# npm1300_qeaa_config3.net
KiCad netlist of a schematic drawn in Altium Designer
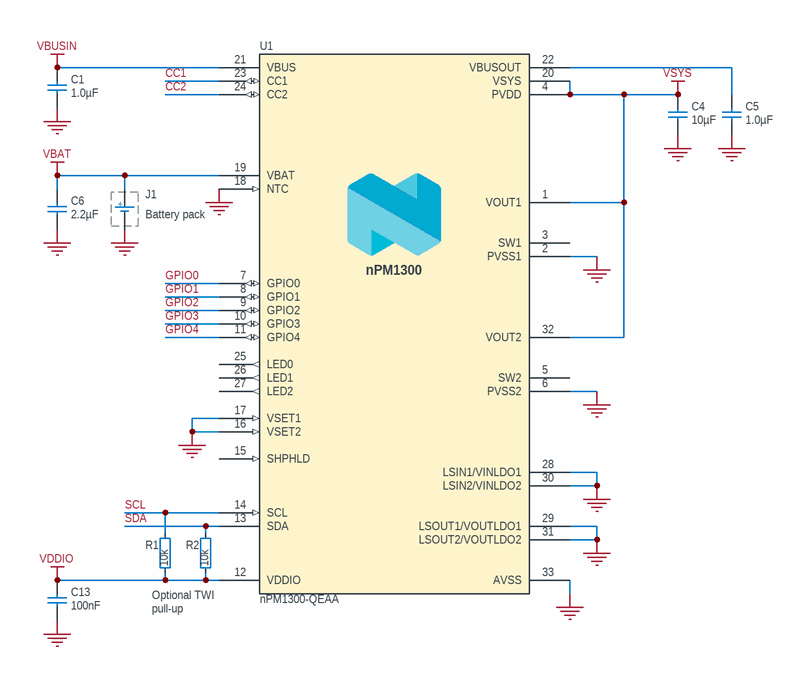
[diagram p0: npm1300_qeaa_config3.SchDoc]

(export (version "E")
  (design (tool "Eeschema 10.0.6"))
  (components
    (comp (ref "C1")
      (value "1.0µF")
      (footprint "CAPC1608X06L")
      (description "Capacitor, Ceramic, 1.0µF 10V X5R 0603,±10%")
      (fields
        (field (name "PART NUMBER") "C0603-1µ0-10V-X5R")
        (field (name "MANUFACTURER") "N.A.")
        (field (name "AUTHOR") "getr")
      )
      (libsource (lib "AltiumLib") (part "CAP"))
    )
    (comp (ref "C4")
      (value "10µF")
      (footprint "CAPC1608X06L")
      (description "Capacitor, X5R, ±20%")
      (fields
        (field (name "PART NUMBER") "C0603-10µ")
        (field (name "MANUFACTURER") "N.A.")
        (field (name "AUTHOR") "rsk")
      )
      (libsource (lib "AltiumLib") (part "CAP"))
    )
    (comp (ref "C5")
      (value "1.0µF")
      (footprint "CAPC1608X06L")
      (description "Capacitor, Ceramic, 1.0µF 10V X5R 0603,±10%")
      (fields
        (field (name "PART NUMBER") "C0603-1µ0-10V-X5R")
        (field (name "MANUFACTURER") "N.A.")
        (field (name "AUTHOR") "getr")
      )
      (libsource (lib "AltiumLib") (part "CAP"))
    )
    (comp (ref "C6")
      (value "2.2µF")
      (footprint "CAPC1608X06L")
      (description "Capacitor, Ceramic, X7R, ±10%, 16V")
      (fields
        (field (name "PART NUMBER") "C0603-2.2µ-16V-X7R")
        (field (name "MANUFACTURER") "Taiyo Yuden")
        (field (name "AUTHOR") "rsk")
      )
      (libsource (lib "AltiumLib") (part "CAP"))
    )
    (comp (ref "C13")
      (value "100nF")
      (footprint "CAPC0603X03L_C")
      (description "Capacitor, X5R, ±10%")
      (fields
        (field (name "PART NUMBER") "C0201-100n")
        (field (name "MANUFACTURER") "N.A.")
        (field (name "AUTHOR") "rsk")
      )
      (libsource (lib "AltiumLib") (part "CAP"))
    )
    (comp (ref "J1")
      (value "Battery pack")
      (footprint "TP_2x1mm_TH")
      (fields
        (field (name "PART NUMBER") "Battery_TP")
        (field (name "MANUFACTURER") "N.A.")
        (field (name "AUTHOR") "rsk")
      )
      (libsource (lib "AltiumLib") (part "Battery_pack"))
    )
    (comp (ref "R1")
      (value "10k")
      (footprint "RESC0603X03L_C")
      (description "Resistor, ±1%, 0.05W")
      (fields
        (field (name "PART NUMBER") "R0201-10k")
        (field (name "MANUFACTURER") "N.A.")
        (field (name "AUTHOR") "rsk")
      )
      (libsource (lib "AltiumLib") (part "RES"))
    )
    (comp (ref "R2")
      (value "10k")
      (footprint "RESC0603X03L_C")
      (description "Resistor, ±1%, 0.05W")
      (fields
        (field (name "PART NUMBER") "R0201-10k")
        (field (name "MANUFACTURER") "N.A.")
        (field (name "AUTHOR") "rsk")
      )
      (libsource (lib "AltiumLib") (part "RES"))
    )
    (comp (ref "U1")
      (value "nPM1300-QEAA")
      (footprint "Nordic_QFN50P500X500X90-33N")
      (fields (field (name "MANUFACTURER") "Nordic Semiconductor") (field (name "AUTHOR") "eisk"))
      (libsource (lib "AltiumLib") (part "nPM1300_QEAA"))
    )
  )
  (nets
    (net (code "1") (name "/CC1") (class "Default")
      (node (ref "U1") (pin "23") (pinfunction "CC1_23") (pintype "bidirectional"))
    )
    (net (code "2") (name "/CC2") (class "Default")
      (node (ref "U1") (pin "24") (pinfunction "CC2_24") (pintype "bidirectional"))
    )
    (net (code "3") (name "/GPIO0") (class "Default")
      (node (ref "U1") (pin "7") (pinfunction "GPIO0_7") (pintype "bidirectional"))
    )
    (net (code "4") (name "/GPIO1") (class "Default")
      (node (ref "U1") (pin "8") (pinfunction "GPIO1_8") (pintype "bidirectional"))
    )
    (net (code "5") (name "/GPIO2") (class "Default")
      (node (ref "U1") (pin "9") (pinfunction "GPIO2_9") (pintype "bidirectional"))
    )
    (net (code "6") (name "/GPIO3") (class "Default")
      (node (ref "U1") (pin "10") (pinfunction "GPIO3_10") (pintype "bidirectional"))
    )
    (net (code "7") (name "/GPIO4") (class "Default")
      (node (ref "U1") (pin "11") (pinfunction "GPIO4_11") (pintype "bidirectional"))
    )
    (net (code "8") (name "/SCL") (class "Default")
      (node (ref "R1") (pin "1") (pinfunction "1_1") (pintype "passive"))
      (node (ref "U1") (pin "14") (pinfunction "SCL_14") (pintype "input"))
    )
    (net (code "9") (name "/SDA") (class "Default")
      (node (ref "R2") (pin "1") (pinfunction "1_1") (pintype "passive"))
      (node (ref "U1") (pin "13") (pinfunction "SDA_13") (pintype "open_collector"))
    )
    (net (code "10") (name "GND") (class "Default")
      (node (ref "C1") (pin "1") (pinfunction "1_1") (pintype "passive"))
      (node (ref "C13") (pin "2") (pinfunction "2_2") (pintype "passive"))
      (node (ref "C4") (pin "1") (pinfunction "1_1") (pintype "passive"))
      (node (ref "C5") (pin "1") (pinfunction "1_1") (pintype "passive"))
      (node (ref "C6") (pin "1") (pinfunction "1_1") (pintype "passive"))
      (node (ref "J1") (pin "1") (pinfunction "GND_1") (pintype "passive"))
      (node (ref "U1") (pin "16") (pinfunction "VSET2_16") (pintype "input"))
      (node (ref "U1") (pin "17") (pinfunction "VSET1_17") (pintype "input"))
      (node (ref "U1") (pin "18") (pinfunction "NTC_18") (pintype "input"))
      (node (ref "U1") (pin "2") (pinfunction "PVSS1_2") (pintype "power_in"))
      (node (ref "U1") (pin "28") (pinfunction "LSIN1/VINLDO1_28") (pintype "power_in"))
      (node (ref "U1") (pin "29") (pinfunction "LSOUT1/VOUTLDO1_29") (pintype "power_in"))
      (node (ref "U1") (pin "30") (pinfunction "LSIN2/VINLDO2_30") (pintype "power_in"))
      (node (ref "U1") (pin "31") (pinfunction "LSOUT2/VOUTLDO2_31") (pintype "power_in"))
      (node (ref "U1") (pin "33") (pinfunction "AVSS_33") (pintype "power_in"))
      (node (ref "U1") (pin "6") (pinfunction "PVSS2_6") (pintype "power_in"))
    )
    (net (code "11") (name "Net-(U1-VBUSOUT)") (class "Default")
      (node (ref "C5") (pin "2") (pinfunction "2_2") (pintype "passive"))
      (node (ref "U1") (pin "22") (pinfunction "VBUSOUT_22") (pintype "power_in"))
    )
    (net (code "12") (name "VBAT") (class "Default")
      (node (ref "C6") (pin "2") (pinfunction "2_2") (pintype "passive"))
      (node (ref "J1") (pin "2") (pinfunction "V+_2") (pintype "passive"))
      (node (ref "U1") (pin "19") (pinfunction "VBAT_19") (pintype "passive"))
    )
    (net (code "13") (name "VBUSIN") (class "Default")
      (node (ref "C1") (pin "2") (pinfunction "2_2") (pintype "passive"))
      (node (ref "U1") (pin "21") (pinfunction "VBUS_21") (pintype "power_in"))
    )
    (net (code "14") (name "VDDIO") (class "Default")
      (node (ref "C13") (pin "1") (pinfunction "1_1") (pintype "passive"))
      (node (ref "R1") (pin "2") (pinfunction "2_2") (pintype "passive"))
      (node (ref "R2") (pin "2") (pinfunction "2_2") (pintype "passive"))
      (node (ref "U1") (pin "12") (pinfunction "VDDIO_12") (pintype "power_in"))
    )
    (net (code "15") (name "VSYS") (class "Default")
      (node (ref "C4") (pin "2") (pinfunction "2_2") (pintype "passive"))
      (node (ref "U1") (pin "1") (pinfunction "VOUT1_1") (pintype "power_in"))
      (node (ref "U1") (pin "20") (pinfunction "VSYS_20") (pintype "power_in"))
      (node (ref "U1") (pin "32") (pinfunction "VOUT2_32") (pintype "power_in"))
      (node (ref "U1") (pin "4") (pinfunction "PVDD_4") (pintype "power_in"))
    )
    (net (code "16") (name "unconnected-(U1-LED0-Pad25)") (class "Default")
      (node (ref "U1") (pin "25") (pinfunction "LED0_25") (pintype "output"))
    )
    (net (code "17") (name "unconnected-(U1-LED1-Pad26)") (class "Default")
      (node (ref "U1") (pin "26") (pinfunction "LED1_26") (pintype "output"))
    )
    (net (code "18") (name "unconnected-(U1-LED2-Pad27)") (class "Default")
      (node (ref "U1") (pin "27") (pinfunction "LED2_27") (pintype "output"))
    )
    (net (code "19") (name "unconnected-(U1-SHPHLD-Pad15)") (class "Default")
      (node (ref "U1") (pin "15") (pinfunction "SHPHLD_15") (pintype "input"))
    )
    (net (code "20") (name "unconnected-(U1-SW1-Pad3)") (class "Default")
      (node (ref "U1") (pin "3") (pinfunction "SW1_3") (pintype "power_in"))
    )
    (net (code "21") (name "unconnected-(U1-SW2-Pad5)") (class "Default")
      (node (ref "U1") (pin "5") (pinfunction "SW2_5") (pintype "power_in"))
    )
  )
)
